# power.net
KiCad netlist of a schematic drawn in Altium Designer
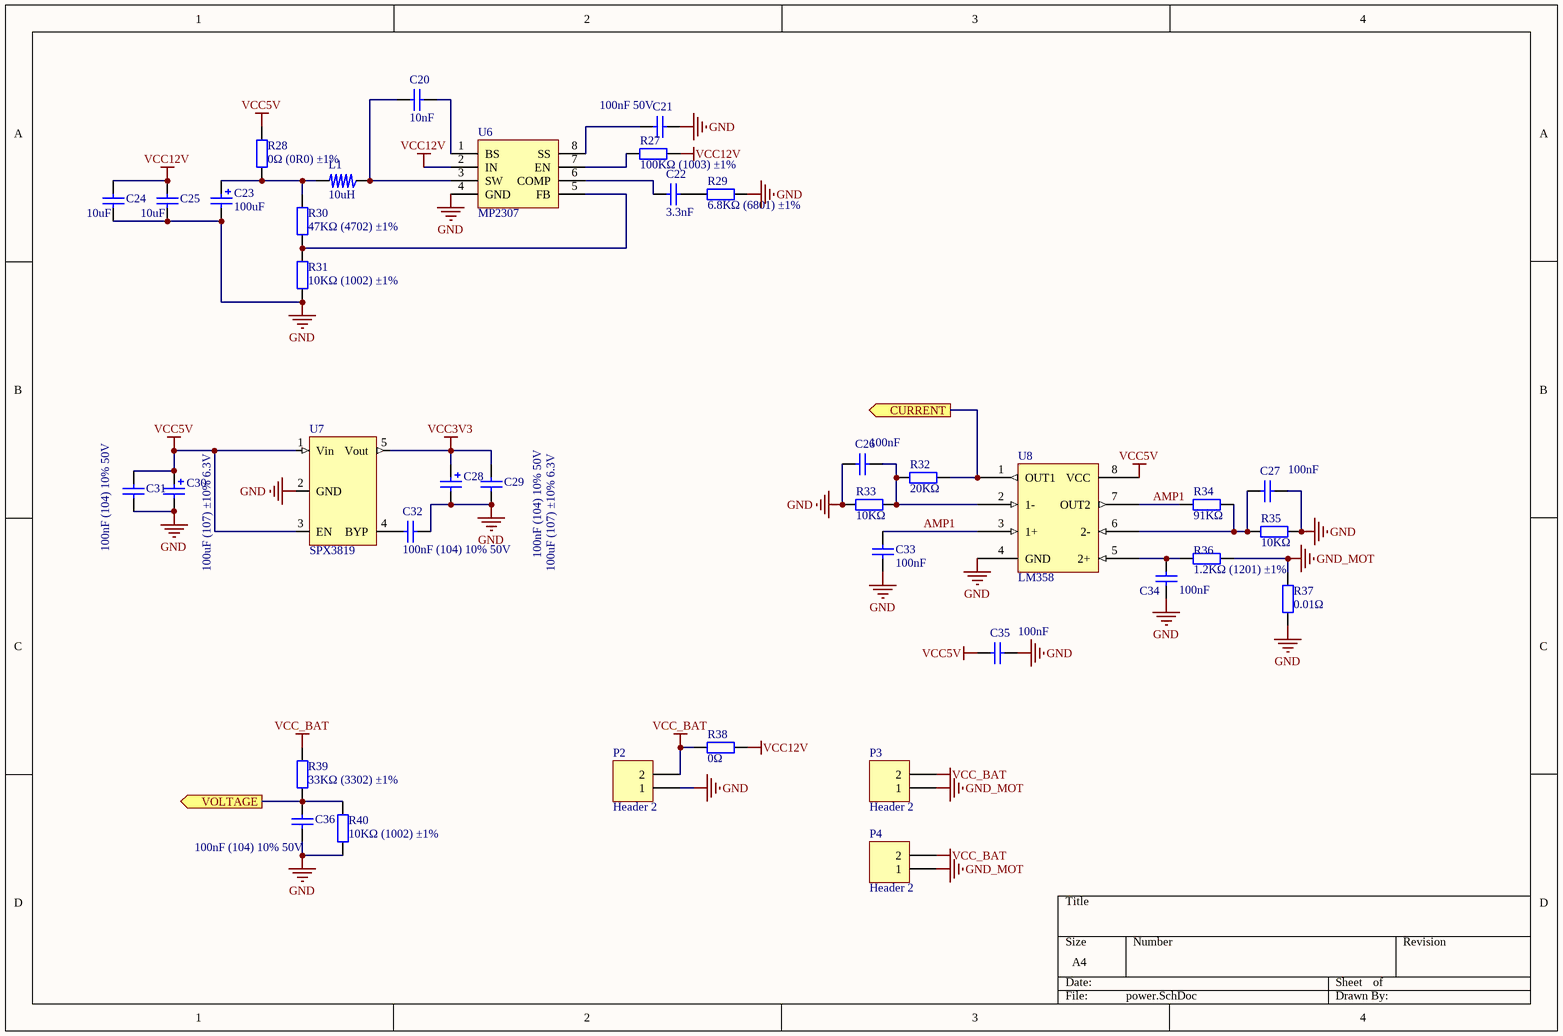
[diagram p0: power.SchDoc]

(export (version "E")
  (design (tool "Eeschema 10.0.6"))
  (components
    (comp (ref "C20")
      (value "10nF")
      (footprint "0603_C")
      (description "贴片电容")
      (libsource (lib "Cap") (part "0603 10nF (103) 10% 50V"))
    )
    (comp (ref "C21")
      (value "100nF 50V")
      (footprint "0603_C")
      (description "贴片电容")
      (libsource (lib "Cap") (part "0603 100nF (104) 10% 50V"))
    )
    (comp (ref "C22")
      (value "3.3nF")
      (footprint "0603_C")
      (description "贴片电容")
      (libsource (lib "Cap") (part "0603 3.3nF (332) 10% 50V"))
    )
    (comp (ref "C23")
      (value "100uF")
      (footprint "CASE-B_3528")
      (description "钽电容")
      (libsource (lib "Cap") (part "3528 100uF (107) 10% 6.3V"))
    )
    (comp (ref "C24")
      (value "10uF")
      (footprint "1206_C")
      (description "贴片电容")
      (libsource (lib "Cap") (part "1206 10uF (106) 10% 50V"))
    )
    (comp (ref "C25")
      (value "10uF")
      (footprint "1206_C")
      (description "贴片电容")
      (libsource (lib "Cap") (part "1206 10uF (106) 10% 50V"))
    )
    (comp (ref "C26")
      (value "100nF")
      (footprint "0603_C")
      (description "贴片电容")
      (libsource (lib "Cap") (part "0603 100nF (104) 10% 50V"))
    )
    (comp (ref "C27")
      (value "100nF")
      (footprint "0603_C")
      (description "贴片电容")
      (libsource (lib "Cap") (part "0603 100nF (104) 10% 50V"))
    )
    (comp (ref "C28")
      (value "100uF (107) ±10% 6.3V")
      (footprint "CASE-B_3528")
      (description "钽电容")
      (libsource (lib "Cap") (part "3528 100uF (107) 10% 6.3V"))
    )
    (comp (ref "C29")
      (value "100nF (104) 10% 50V")
      (footprint "0603_C")
      (description "贴片电容")
      (libsource (lib "Cap") (part "0603 100nF (104) 10% 50V"))
    )
    (comp (ref "C30")
      (value "100uF (107) ±10% 6.3V")
      (footprint "CASE-B_3528")
      (description "钽电容")
      (libsource (lib "Cap") (part "3528 100uF (107) 10% 6.3V"))
    )
    (comp (ref "C31")
      (value "100nF (104) 10% 50V")
      (footprint "0603_C")
      (description "贴片电容")
      (libsource (lib "Cap") (part "0603 100nF (104) 10% 50V"))
    )
    (comp (ref "C32")
      (value "100nF (104) 10% 50V")
      (footprint "0603_C")
      (description "贴片电容")
      (libsource (lib "Cap") (part "0603 100nF (104) 10% 50V"))
    )
    (comp (ref "C33")
      (value "100nF")
      (footprint "0603_C")
      (description "贴片电容")
      (libsource (lib "Cap") (part "0603 100nF (104) 10% 50V"))
    )
    (comp (ref "C34")
      (value "100nF")
      (footprint "0603_C")
      (description "贴片电容")
      (libsource (lib "Cap") (part "0603 100nF (104) 10% 50V"))
    )
    (comp (ref "C35")
      (value "100nF")
      (footprint "0603_C")
      (description "贴片电容")
      (libsource (lib "Cap") (part "0603 100nF (104) 10% 50V"))
    )
    (comp (ref "C36")
      (value "100nF (104) 10% 50V")
      (footprint "0603_C")
      (description "贴片电容")
      (libsource (lib "Cap") (part "0603 100nF (104) 10% 50V"))
    )
    (comp (ref "L1") (value "10uH") (footprint "L_SOP74") (libsource (lib "EXPLORER") (part "L_SOP")))
    (comp (ref "P2")
      (value "Header 2")
      (footprint "HT508R")
      (description "Header, 2-Pin")
      (fields (field (name "PUBLISHER") "Altium Limited"))
      (libsource (lib "Miscellaneous Connectors") (part "Header 2"))
    )
    (comp (ref "P3")
      (value "Header 2")
      (footprint "HT508R")
      (description "Header, 2-Pin")
      (fields (field (name "PUBLISHER") "Altium Limited"))
      (libsource (lib "Miscellaneous Connectors") (part "Header 2"))
    )
    (comp (ref "P4")
      (value "Header 2")
      (footprint "HT508R")
      (description "Header, 2-Pin")
      (fields (field (name "PUBLISHER") "Altium Limited"))
      (libsource (lib "Miscellaneous Connectors") (part "Header 2"))
    )
    (comp (ref "R27")
      (value "100KΩ (1003) ±1%")
      (footprint "0603_R")
      (description "贴片电阻")
      (libsource (lib "RES") (part "0603 100KΩ (1003) 1%"))
    )
    (comp (ref "R28")
      (value "0Ω (0R0) ±1%")
      (footprint "0603_R")
      (description "贴片电阻")
      (libsource (lib "RES") (part "0603 0Ω (0R0) 1%"))
    )
    (comp (ref "R29")
      (value "6.8KΩ (6801) ±1%")
      (footprint "0603_R")
      (description "贴片电阻")
      (libsource (lib "RES") (part "0603 6.8KΩ (6801) 1%"))
    )
    (comp (ref "R30")
      (value "47KΩ (4702) ±1%")
      (footprint "0603_R")
      (description "贴片电阻")
      (libsource (lib "RES") (part "0603 47KΩ (4702) 1%"))
    )
    (comp (ref "R31")
      (value "10KΩ (1002) ±1%")
      (footprint "0603_R")
      (description "贴片电阻")
      (libsource (lib "") (part "0603 10KΩ (1002) 1%_1"))
    )
    (comp (ref "R32")
      (value "20KΩ")
      (footprint "0603_R")
      (description "贴片电阻")
      (libsource (lib "RES") (part "0603 20KΩ (2002) 1%"))
    )
    (comp (ref "R33")
      (value "10KΩ")
      (footprint "0603_R")
      (description "贴片电阻")
      (libsource (lib "RES") (part "0603 10KΩ (1002) 1%"))
    )
    (comp (ref "R34")
      (value "91KΩ")
      (footprint "0603_R")
      (description "贴片电阻")
      (libsource (lib "RES") (part "0603 91KΩ (9102) 1%"))
    )
    (comp (ref "R35")
      (value "10KΩ")
      (footprint "0603_R")
      (description "贴片电阻")
      (libsource (lib "RES") (part "0603 10KΩ (1002) 1%"))
    )
    (comp (ref "R36")
      (value "1.2KΩ (1201) ±1%")
      (footprint "0603_R")
      (description "贴片电阻")
      (libsource (lib "RES") (part "0603 1.2KΩ (1201) 1%"))
    )
    (comp (ref "R37")
      (value "0.01Ω")
      (footprint "2512_R")
      (description "贴片电阻")
      (libsource (lib "RES") (part "1206 100Ω (1000) 1%"))
    )
    (comp (ref "R38")
      (value "0Ω")
      (footprint "1206_R")
      (description "自恢复保险丝")
      (libsource (lib "") (part "1206 100Ω (1000) 1%_1"))
    )
    (comp (ref "R39")
      (value "33KΩ (3302) ±1%")
      (footprint "0603_R")
      (description "贴片电阻")
      (libsource (lib "RES") (part "0603 33KΩ (3302) 1%"))
    )
    (comp (ref "R40")
      (value "10KΩ (1002) ±1%")
      (footprint "0603_R")
      (description "贴片电阻")
      (libsource (lib "") (part "0603 10KΩ (1002) 1%_1"))
    )
    (comp (ref "U6")
      (value "MP2307")
      (footprint "SOIC-8_EP_150mil")
      (description "DC-DC降压芯片")
      (libsource (lib "*") (part "MP2307"))
    )
    (comp (ref "U7") (value "SPX3819") (footprint "SOT25-5") (libsource (lib "MySchlib") (part "SPX3819")))
    (comp (ref "U8") (value "LM358") (footprint "SOIC-8_150mil") (libsource (lib "MySchlib") (part "LM358")))
  )
  (nets
    (net (code "1") (name "/AMP1") (class "Default")
      (node (ref "C33") (pin "2") (pinfunction "2_2") (pintype "passive"))
      (node (ref "R34") (pin "1") (pinfunction "1_1") (pintype "passive"))
      (node (ref "U8") (pin "3") (pinfunction "1+_3") (pintype "input"))
      (node (ref "U8") (pin "7") (pinfunction "OUT2_7") (pintype "output"))
    )
    (net (code "2") (name "/CURRENT") (class "Default")
      (node (ref "R32") (pin "2") (pinfunction "2_2") (pintype "passive"))
      (node (ref "U8") (pin "1") (pinfunction "OUT1_1") (pintype "output"))
    )
    (net (code "3") (name "/VOLTAGE") (class "Default")
      (node (ref "C36") (pin "1") (pinfunction "1_1") (pintype "passive"))
      (node (ref "R39") (pin "1") (pinfunction "1_1") (pintype "passive"))
      (node (ref "R40") (pin "2") (pinfunction "2_2") (pintype "passive"))
    )
    (net (code "4") (name "GND") (class "Default")
      (node (ref "C21") (pin "1") (pinfunction "1_1") (pintype "passive"))
      (node (ref "C23") (pin "2") (pinfunction "2_2") (pintype "passive"))
      (node (ref "C24") (pin "1") (pinfunction "1_1") (pintype "passive"))
      (node (ref "C25") (pin "1") (pinfunction "1_1") (pintype "passive"))
      (node (ref "C26") (pin "1") (pinfunction "1_1") (pintype "passive"))
      (node (ref "C27") (pin "2") (pinfunction "2_2") (pintype "passive"))
      (node (ref "C28") (pin "2") (pinfunction "2_2") (pintype "passive"))
      (node (ref "C29") (pin "1") (pinfunction "1_1") (pintype "passive"))
      (node (ref "C30") (pin "2") (pinfunction "2_2") (pintype "passive"))
      (node (ref "C31") (pin "2") (pinfunction "2_2") (pintype "passive"))
      (node (ref "C32") (pin "1") (pinfunction "1_1") (pintype "passive"))
      (node (ref "C33") (pin "1") (pinfunction "1_1") (pintype "passive"))
      (node (ref "C34") (pin "1") (pinfunction "1_1") (pintype "passive"))
      (node (ref "C35") (pin "2") (pinfunction "2_2") (pintype "passive"))
      (node (ref "C36") (pin "2") (pinfunction "2_2") (pintype "passive"))
      (node (ref "P2") (pin "1") (pinfunction "1_1") (pintype "passive"))
      (node (ref "R29") (pin "2") (pinfunction "2_2") (pintype "passive"))
      (node (ref "R31") (pin "1") (pinfunction "1_1") (pintype "passive"))
      (node (ref "R33") (pin "2") (pinfunction "2_2") (pintype "passive"))
      (node (ref "R35") (pin "1") (pinfunction "1_1") (pintype "passive"))
      (node (ref "R37") (pin "2") (pinfunction "2_2") (pintype "passive"))
      (node (ref "R40") (pin "1") (pinfunction "1_1") (pintype "passive"))
      (node (ref "U6") (pin "4") (pinfunction "GND_4") (pintype "passive"))
      (node (ref "U7") (pin "2") (pinfunction "GND_2") (pintype "passive"))
      (node (ref "U8") (pin "4") (pinfunction "GND_4") (pintype "power_in"))
    )
    (net (code "5") (name "GND_MOT") (class "Default")
      (node (ref "P3") (pin "1") (pinfunction "1_1") (pintype "passive"))
      (node (ref "P4") (pin "1") (pinfunction "1_1") (pintype "passive"))
      (node (ref "R36") (pin "2") (pinfunction "2_2") (pintype "passive"))
      (node (ref "R37") (pin "1") (pinfunction "1_1") (pintype "passive"))
    )
    (net (code "6") (name "Net-(C22-Pad2)") (class "Default")
      (node (ref "C22") (pin "2") (pinfunction "2_2") (pintype "passive"))
      (node (ref "R29") (pin "1") (pinfunction "1_1") (pintype "passive"))
    )
    (net (code "7") (name "Net-(C23-Pad1)") (class "Default")
      (node (ref "C23") (pin "1") (pinfunction "1_1") (pintype "passive"))
      (node (ref "L1") (pin "2") (pinfunction "2_2") (pintype "passive"))
      (node (ref "R28") (pin "1") (pinfunction "1_1") (pintype "passive"))
      (node (ref "R30") (pin "2") (pinfunction "2_2") (pintype "passive"))
    )
    (net (code "8") (name "Net-(U6-BS)") (class "Default")
      (node (ref "C20") (pin "1") (pinfunction "1_1") (pintype "passive"))
      (node (ref "U6") (pin "1") (pinfunction "BS_1") (pintype "passive"))
    )
    (net (code "9") (name "Net-(U6-COMP)") (class "Default")
      (node (ref "C22") (pin "1") (pinfunction "1_1") (pintype "passive"))
      (node (ref "U6") (pin "6") (pinfunction "COMP_6") (pintype "passive"))
    )
    (net (code "10") (name "Net-(U6-EN)") (class "Default")
      (node (ref "R27") (pin "1") (pinfunction "1_1") (pintype "passive"))
      (node (ref "U6") (pin "7") (pinfunction "EN_7") (pintype "passive"))
    )
    (net (code "11") (name "Net-(U6-FB)") (class "Default")
      (node (ref "R30") (pin "1") (pinfunction "1_1") (pintype "passive"))
      (node (ref "R31") (pin "2") (pinfunction "2_2") (pintype "passive"))
      (node (ref "U6") (pin "5") (pinfunction "FB_5") (pintype "passive"))
    )
    (net (code "12") (name "Net-(U6-SS)") (class "Default")
      (node (ref "C21") (pin "2") (pinfunction "2_2") (pintype "passive"))
      (node (ref "U6") (pin "8") (pinfunction "SS_8") (pintype "passive"))
    )
    (net (code "13") (name "Net-(U6-SW)") (class "Default")
      (node (ref "C20") (pin "2") (pinfunction "2_2") (pintype "passive"))
      (node (ref "L1") (pin "1") (pinfunction "1_1") (pintype "passive"))
      (node (ref "U6") (pin "3") (pinfunction "SW_3") (pintype "passive"))
    )
    (net (code "14") (name "Net-(U7-BYP)") (class "Default")
      (node (ref "C32") (pin "2") (pinfunction "2_2") (pintype "passive"))
      (node (ref "U7") (pin "4") (pinfunction "BYP_4") (pintype "passive"))
    )
    (net (code "15") (name "Net-(U8-1-)") (class "Default")
      (node (ref "C26") (pin "2") (pinfunction "2_2") (pintype "passive"))
      (node (ref "R32") (pin "1") (pinfunction "1_1") (pintype "passive"))
      (node (ref "R33") (pin "1") (pinfunction "1_1") (pintype "passive"))
      (node (ref "U8") (pin "2") (pinfunction "1-_2") (pintype "input"))
    )
    (net (code "16") (name "Net-(U8-2+)") (class "Default")
      (node (ref "C34") (pin "2") (pinfunction "2_2") (pintype "passive"))
      (node (ref "R36") (pin "1") (pinfunction "1_1") (pintype "passive"))
      (node (ref "U8") (pin "5") (pinfunction "2+_5") (pintype "input"))
    )
    (net (code "17") (name "Net-(U8-2-)") (class "Default")
      (node (ref "C27") (pin "1") (pinfunction "1_1") (pintype "passive"))
      (node (ref "R34") (pin "2") (pinfunction "2_2") (pintype "passive"))
      (node (ref "R35") (pin "2") (pinfunction "2_2") (pintype "passive"))
      (node (ref "U8") (pin "6") (pinfunction "2-_6") (pintype "input"))
    )
    (net (code "18") (name "VCC3V3") (class "Default")
      (node (ref "C28") (pin "1") (pinfunction "1_1") (pintype "passive"))
      (node (ref "C29") (pin "2") (pinfunction "2_2") (pintype "passive"))
      (node (ref "U7") (pin "5") (pinfunction "Vout_5") (pintype "output"))
    )
    (net (code "19") (name "VCC5V") (class "Default")
      (node (ref "C30") (pin "1") (pinfunction "1_1") (pintype "passive"))
      (node (ref "C31") (pin "1") (pinfunction "1_1") (pintype "passive"))
      (node (ref "C35") (pin "1") (pinfunction "1_1") (pintype "passive"))
      (node (ref "R28") (pin "2") (pinfunction "2_2") (pintype "passive"))
      (node (ref "U7") (pin "1") (pinfunction "Vin_1") (pintype "input"))
      (node (ref "U7") (pin "3") (pinfunction "EN_3") (pintype "passive"))
      (node (ref "U8") (pin "8") (pinfunction "VCC_8") (pintype "power_in"))
    )
    (net (code "20") (name "VCC12V") (class "Default")
      (node (ref "C24") (pin "2") (pinfunction "2_2") (pintype "passive"))
      (node (ref "C25") (pin "2") (pinfunction "2_2") (pintype "passive"))
      (node (ref "R27") (pin "2") (pinfunction "2_2") (pintype "passive"))
      (node (ref "R38") (pin "1") (pinfunction "1_1") (pintype "passive"))
      (node (ref "U6") (pin "2") (pinfunction "IN_2") (pintype "passive"))
    )
    (net (code "21") (name "VCC_BAT") (class "Default")
      (node (ref "P2") (pin "2") (pinfunction "2_2") (pintype "passive"))
      (node (ref "P3") (pin "2") (pinfunction "2_2") (pintype "passive"))
      (node (ref "P4") (pin "2") (pinfunction "2_2") (pintype "passive"))
      (node (ref "R38") (pin "2") (pinfunction "2_2") (pintype "passive"))
      (node (ref "R39") (pin "2") (pinfunction "2_2") (pintype "passive"))
    )
  )
)
